# BiphasicBoard.net
KiCad netlist of a schematic drawn in EAGLE
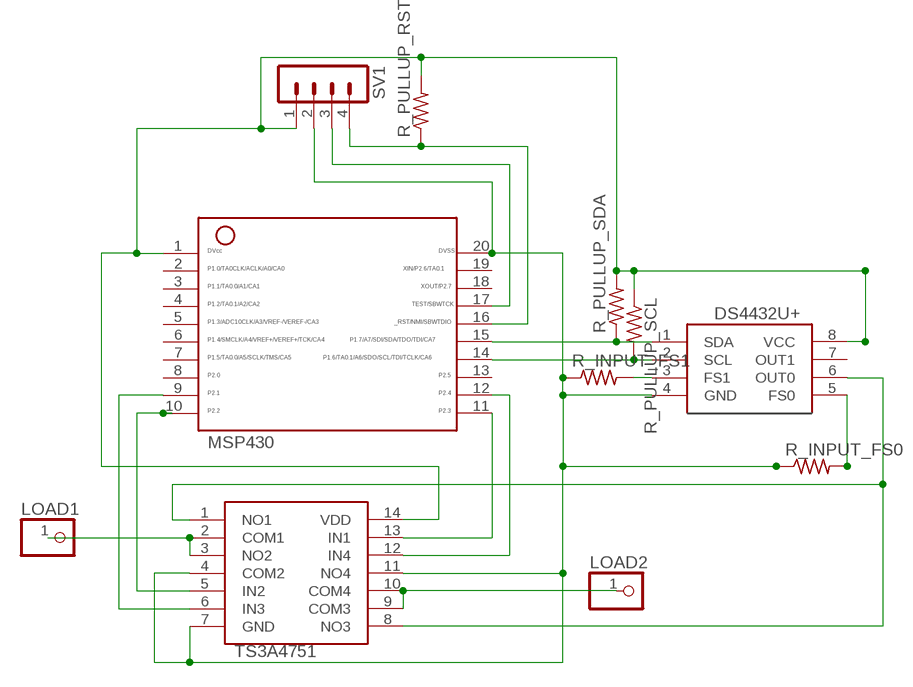
[diagram p0: schematic, sheet 1]

(export (version "E")
  (design (tool "Eeschema 10.0.6"))
  (components
    (comp (ref "DS4432U+")
      (value "DS4432U+")
      (footprint "eagle-import:8_PIN")
      (libsource (lib "eagle-import") (part "DS4432U+"))
    )
    (comp (ref "LOAD1")
      (value "PINHD-1X1")
      (footprint "eagle-import:1X01")
      (libsource (lib "eagle-import") (part "PINHD-1X1"))
    )
    (comp (ref "LOAD2")
      (value "PINHD-1X1")
      (footprint "eagle-import:1X01")
      (libsource (lib "eagle-import") (part "PINHD-1X1"))
    )
    (comp (ref "MSP430")
      (value "MSP430")
      (footprint "eagle-import:20_PIN")
      (libsource (lib "eagle-import") (part "MSP430"))
    )
    (comp (ref "R_INPUT_FS0")
      (value "R-US_R0603")
      (footprint "eagle-import:R0603")
      (libsource (lib "eagle-import") (part "R-US_R0603"))
    )
    (comp (ref "R_INPUT_FS1")
      (value "R-US_R0603")
      (footprint "eagle-import:R0603")
      (libsource (lib "eagle-import") (part "R-US_R0603"))
    )
    (comp (ref "R_PULLUP_RST")
      (value "R-US_R0603")
      (footprint "eagle-import:R0603")
      (libsource (lib "eagle-import") (part "R-US_R0603"))
    )
    (comp (ref "R_PULLUP_SCL")
      (value "R-US_R0603")
      (footprint "eagle-import:R0603")
      (libsource (lib "eagle-import") (part "R-US_R0603"))
    )
    (comp (ref "R_PULLUP_SDA")
      (value "R-US_R0603")
      (footprint "eagle-import:R0603")
      (libsource (lib "eagle-import") (part "R-US_R0603"))
    )
    (comp (ref "SV1")
      (value "MA04-1")
      (footprint "eagle-import:MA04-1")
      (libsource (lib "eagle-import") (part "MA04-1"))
    )
    (comp (ref "TS3A4751")
      (value "TS3A4751")
      (footprint "eagle-import:14_PIN")
      (libsource (lib "eagle-import") (part "TS3A4751"))
    )
  )
  (nets
    (net (code "1") (name "Net-(DS4432U+-FS0)") (class "Default")
      (node (ref "DS4432U+") (pin "5") (pinfunction "FS0_5") (pintype "bidirectional"))
      (node (ref "R_INPUT_FS0") (pin "2") (pinfunction "2_2") (pintype "passive"))
    )
    (net (code "2") (name "Net-(DS4432U+-FS1)") (class "Default")
      (node (ref "DS4432U+") (pin "3") (pinfunction "FS1_3") (pintype "bidirectional"))
      (node (ref "R_INPUT_FS1") (pin "2") (pinfunction "2_2") (pintype "passive"))
    )
    (net (code "3") (name "Net-(DS4432U+-GND)") (class "Default")
      (node (ref "DS4432U+") (pin "4") (pinfunction "GND_4") (pintype "bidirectional"))
      (node (ref "MSP430") (pin "20") (pinfunction "20_20") (pintype "bidirectional"))
      (node (ref "R_INPUT_FS0") (pin "1") (pinfunction "1_1") (pintype "passive"))
      (node (ref "R_INPUT_FS1") (pin "1") (pinfunction "1_1") (pintype "passive"))
      (node (ref "SV1") (pin "2") (pinfunction "2_2") (pintype "passive"))
      (node (ref "TS3A4751") (pin "11") (pinfunction "NO4_11") (pintype "bidirectional"))
      (node (ref "TS3A4751") (pin "4") (pinfunction "COM2_4") (pintype "bidirectional"))
      (node (ref "TS3A4751") (pin "7") (pinfunction "GND_7") (pintype "bidirectional"))
    )
    (net (code "4") (name "Net-(DS4432U+-OUT0)") (class "Default")
      (node (ref "DS4432U+") (pin "6") (pinfunction "OUT0_6") (pintype "bidirectional"))
      (node (ref "TS3A4751") (pin "1") (pinfunction "NO1_1") (pintype "bidirectional"))
      (node (ref "TS3A4751") (pin "8") (pinfunction "NO3_8") (pintype "bidirectional"))
    )
    (net (code "5") (name "Net-(DS4432U+-SCL)") (class "Default")
      (node (ref "DS4432U+") (pin "2") (pinfunction "SCL_2") (pintype "bidirectional"))
      (node (ref "MSP430") (pin "14") (pinfunction "14_14") (pintype "bidirectional"))
      (node (ref "R_PULLUP_SCL") (pin "2") (pinfunction "2_2") (pintype "passive"))
    )
    (net (code "6") (name "Net-(DS4432U+-SDA)") (class "Default")
      (node (ref "DS4432U+") (pin "1") (pinfunction "SDA_1") (pintype "bidirectional"))
      (node (ref "MSP430") (pin "15") (pinfunction "15_15") (pintype "bidirectional"))
      (node (ref "R_PULLUP_SDA") (pin "1") (pinfunction "1_1") (pintype "passive"))
    )
    (net (code "7") (name "Net-(DS4432U+-VCC)") (class "Default")
      (node (ref "DS4432U+") (pin "8") (pinfunction "VCC_8") (pintype "bidirectional"))
      (node (ref "MSP430") (pin "1") (pinfunction "1_1") (pintype "bidirectional"))
      (node (ref "R_PULLUP_RST") (pin "2") (pinfunction "2_2") (pintype "passive"))
      (node (ref "R_PULLUP_SCL") (pin "1") (pinfunction "1_1") (pintype "passive"))
      (node (ref "R_PULLUP_SDA") (pin "2") (pinfunction "2_2") (pintype "passive"))
      (node (ref "SV1") (pin "1") (pinfunction "1_1") (pintype "passive"))
      (node (ref "TS3A4751") (pin "14") (pinfunction "VDD_14") (pintype "bidirectional"))
    )
    (net (code "8") (name "Net-(MSP430-Pad16)") (class "Default")
      (node (ref "MSP430") (pin "16") (pinfunction "16_16") (pintype "bidirectional"))
      (node (ref "R_PULLUP_RST") (pin "1") (pinfunction "1_1") (pintype "passive"))
      (node (ref "SV1") (pin "4") (pinfunction "4_4") (pintype "passive"))
    )
    (net (code "9") (name "Net-(MSP430-Pad17)") (class "Default")
      (node (ref "MSP430") (pin "17") (pinfunction "17_17") (pintype "bidirectional"))
      (node (ref "SV1") (pin "3") (pinfunction "3_3") (pintype "passive"))
    )
    (net (code "10") (name "Net-(TS3A4751-COM1)") (class "Default")
      (node (ref "LOAD1") (pin "1") (pinfunction "1_1") (pintype "passive"))
      (node (ref "TS3A4751") (pin "2") (pinfunction "COM1_2") (pintype "bidirectional"))
      (node (ref "TS3A4751") (pin "3") (pinfunction "NO2_3") (pintype "bidirectional"))
    )
    (net (code "11") (name "Net-(TS3A4751-COM3)") (class "Default")
      (node (ref "LOAD2") (pin "1") (pinfunction "1_1") (pintype "passive"))
      (node (ref "TS3A4751") (pin "10") (pinfunction "COM4_10") (pintype "bidirectional"))
      (node (ref "TS3A4751") (pin "9") (pinfunction "COM3_9") (pintype "bidirectional"))
    )
    (net (code "12") (name "Net-(TS3A4751-IN1)") (class "Default")
      (node (ref "MSP430") (pin "11") (pinfunction "11_11") (pintype "bidirectional"))
      (node (ref "TS3A4751") (pin "13") (pinfunction "IN1_13") (pintype "bidirectional"))
    )
    (net (code "13") (name "Net-(TS3A4751-IN2)") (class "Default")
      (node (ref "MSP430") (pin "10") (pinfunction "10_10") (pintype "bidirectional"))
      (node (ref "TS3A4751") (pin "5") (pinfunction "IN2_5") (pintype "bidirectional"))
    )
    (net (code "14") (name "Net-(TS3A4751-IN3)") (class "Default")
      (node (ref "MSP430") (pin "9") (pinfunction "9_9") (pintype "bidirectional"))
      (node (ref "TS3A4751") (pin "6") (pinfunction "IN3_6") (pintype "bidirectional"))
    )
    (net (code "15") (name "Net-(TS3A4751-IN4)") (class "Default")
      (node (ref "MSP430") (pin "12") (pinfunction "12_12") (pintype "bidirectional"))
      (node (ref "TS3A4751") (pin "12") (pinfunction "IN4_12") (pintype "bidirectional"))
    )
    (net (code "16") (name "unconnected-(DS4432U+-OUT1-Pad7)") (class "Default")
      (node (ref "DS4432U+") (pin "7") (pinfunction "OUT1_7") (pintype "bidirectional"))
    )
    (net (code "17") (name "unconnected-(MSP430-Pad2)") (class "Default")
      (node (ref "MSP430") (pin "2") (pinfunction "2_2") (pintype "bidirectional"))
    )
    (net (code "18") (name "unconnected-(MSP430-Pad3)") (class "Default")
      (node (ref "MSP430") (pin "3") (pinfunction "3_3") (pintype "bidirectional"))
    )
    (net (code "19") (name "unconnected-(MSP430-Pad4)") (class "Default")
      (node (ref "MSP430") (pin "4") (pinfunction "4_4") (pintype "bidirectional"))
    )
    (net (code "20") (name "unconnected-(MSP430-Pad5)") (class "Default")
      (node (ref "MSP430") (pin "5") (pinfunction "5_5") (pintype "bidirectional"))
    )
    (net (code "21") (name "unconnected-(MSP430-Pad6)") (class "Default")
      (node (ref "MSP430") (pin "6") (pinfunction "6_6") (pintype "bidirectional"))
    )
    (net (code "22") (name "unconnected-(MSP430-Pad7)") (class "Default")
      (node (ref "MSP430") (pin "7") (pinfunction "7_7") (pintype "bidirectional"))
    )
    (net (code "23") (name "unconnected-(MSP430-Pad8)") (class "Default")
      (node (ref "MSP430") (pin "8") (pinfunction "8_8") (pintype "bidirectional"))
    )
    (net (code "24") (name "unconnected-(MSP430-Pad13)") (class "Default")
      (node (ref "MSP430") (pin "13") (pinfunction "13_13") (pintype "bidirectional"))
    )
    (net (code "25") (name "unconnected-(MSP430-Pad18)") (class "Default")
      (node (ref "MSP430") (pin "18") (pinfunction "18_18") (pintype "bidirectional"))
    )
    (net (code "26") (name "unconnected-(MSP430-Pad19)") (class "Default")
      (node (ref "MSP430") (pin "19") (pinfunction "19_19") (pintype "bidirectional"))
    )
  )
)
